# schematic.net
KiCad netlist of a schematic drawn in EasyEDA
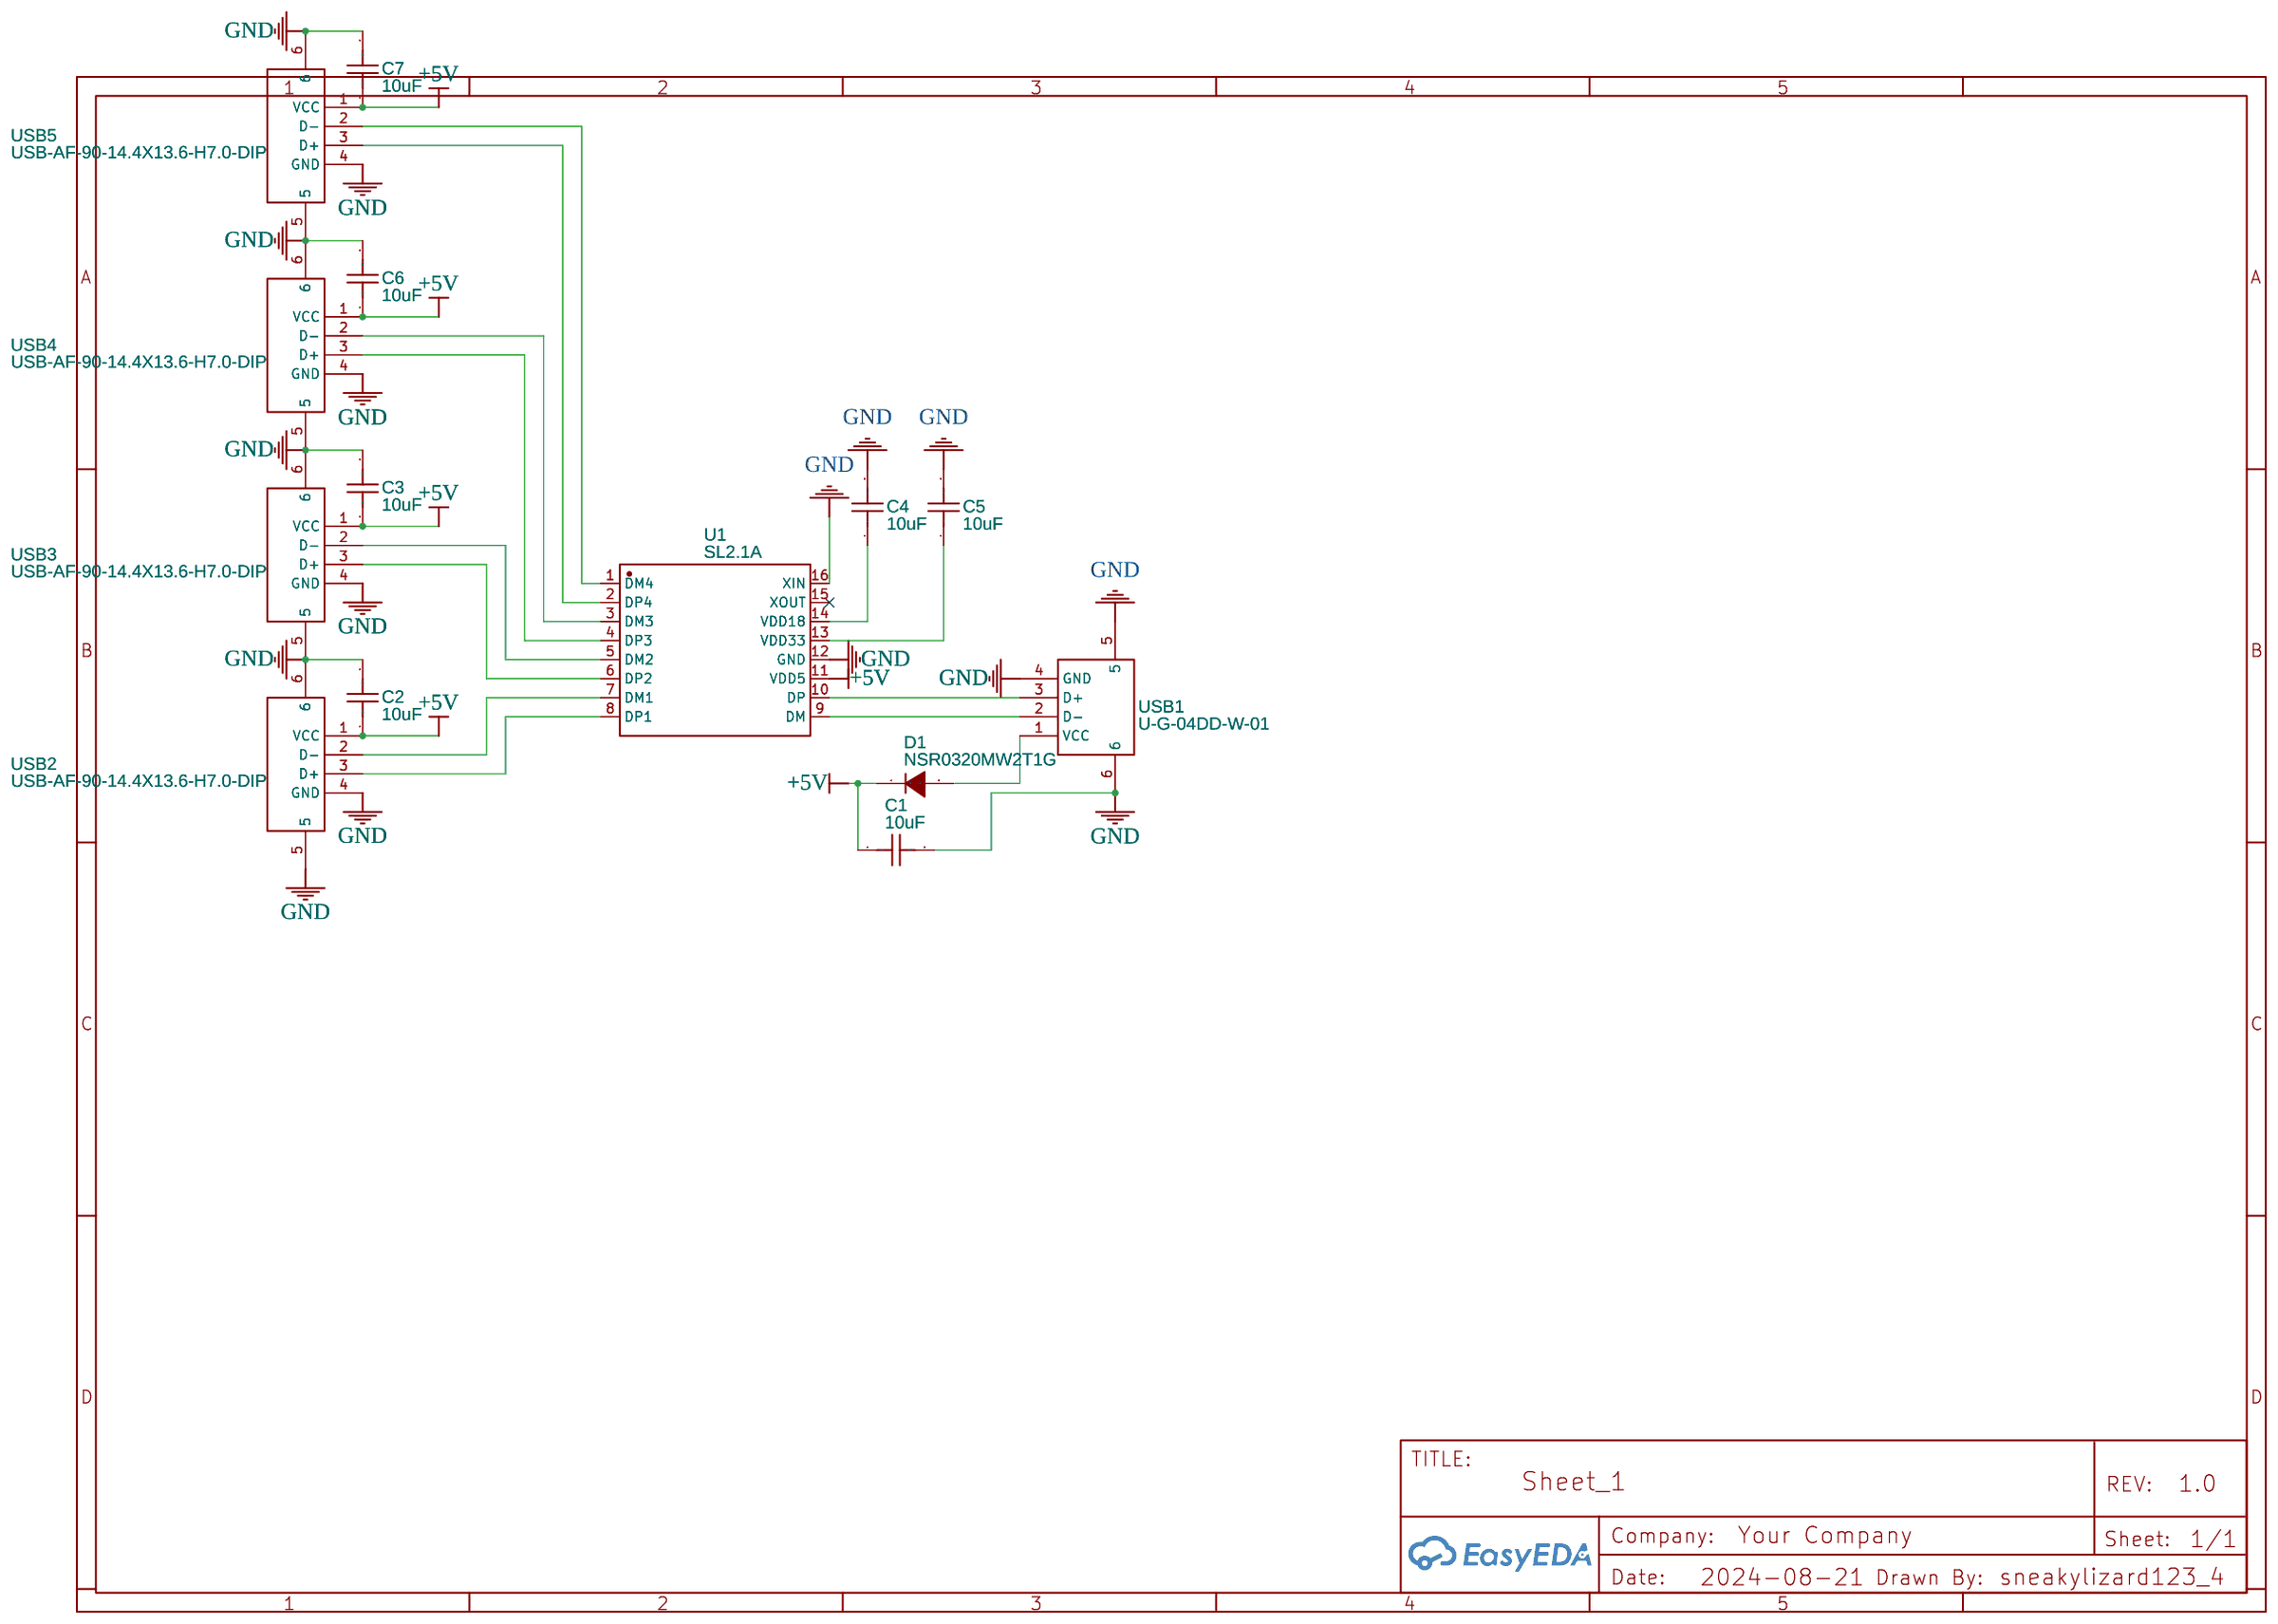
[diagram p0: schematic sheet]

(export (version "E")
  (design (tool "Eeschema 10.0.6"))
  (components
    (comp (ref "C1")
      (value "10uF")
      (fields
        (field (name "Manufacturer Part") "CL10A106KP8NNNC")
        (field (name "Manufacturer") "SAMSUNG(三星)")
      )
      (libsource (lib "") (part "CL10A106KP8NNNC_1"))
    )
    (comp (ref "C2")
      (value "10uF")
      (fields
        (field (name "Manufacturer Part") "CL10A106KP8NNNC")
        (field (name "Manufacturer") "SAMSUNG(三星)")
      )
      (libsource (lib "") (part "CL10A106KP8NNNC"))
    )
    (comp (ref "C3")
      (value "10uF")
      (fields
        (field (name "Manufacturer Part") "CL10A106KP8NNNC")
        (field (name "Manufacturer") "SAMSUNG(三星)")
      )
      (libsource (lib "") (part "CL10A106KP8NNNC"))
    )
    (comp (ref "C4")
      (value "10uF")
      (fields
        (field (name "Manufacturer Part") "CL10A106KP8NNNC")
        (field (name "Manufacturer") "SAMSUNG(三星)")
      )
      (libsource (lib "") (part "CL10A106KP8NNNC"))
    )
    (comp (ref "C5")
      (value "10uF")
      (fields
        (field (name "Manufacturer Part") "CL10A106KP8NNNC")
        (field (name "Manufacturer") "SAMSUNG(三星)")
      )
      (libsource (lib "") (part "CL10A106KP8NNNC"))
    )
    (comp (ref "C6")
      (value "10uF")
      (fields
        (field (name "Manufacturer Part") "CL10A106KP8NNNC")
        (field (name "Manufacturer") "SAMSUNG(三星)")
      )
      (libsource (lib "") (part "CL10A106KP8NNNC"))
    )
    (comp (ref "C7")
      (value "10uF")
      (fields
        (field (name "Manufacturer Part") "CL10A106KP8NNNC")
        (field (name "Manufacturer") "SAMSUNG(三星)")
      )
      (libsource (lib "") (part "CL10A106KP8NNNC"))
    )
    (comp (ref "D1")
      (value "NSR0320MW2T1G")
      (fields (field (name "Manufacturer") "onsemi(安森美)"))
      (libsource (lib "") (part "NSR0320MW2T1G"))
    )
    (comp (ref "U1")
      (value "SL2.1A")
      (fields (field (name "Manufacturer") "CoreChips(和芯润德)"))
      (libsource (lib "") (part "SL2.1A"))
    )
    (comp (ref "USB1")
      (value "U-G-04DD-W-01")
      (fields (field (name "Manufacturer Part") "U-G-O4DD-W-1") (field (name "Manufacturer") "韩国韩荣"))
      (libsource (lib "") (part "U-G-04DD-W-01"))
    )
    (comp (ref "USB2")
      (value "USB-AF-90-14.4X13.6-H7.0-DIP")
      (fields (field (name "Manufacturer Part") "903-131A1011D10100") (field (name "Manufacturer") "精拓金"))
      (libsource (lib "") (part "USB-AF-90-14.4X13.6-H7.0-DIP"))
    )
    (comp (ref "USB3")
      (value "USB-AF-90-14.4X13.6-H7.0-DIP")
      (fields (field (name "Manufacturer Part") "903-131A1011D10100") (field (name "Manufacturer") "精拓金"))
      (libsource (lib "") (part "USB-AF-90-14.4X13.6-H7.0-DIP"))
    )
    (comp (ref "USB4")
      (value "USB-AF-90-14.4X13.6-H7.0-DIP")
      (fields (field (name "Manufacturer Part") "903-131A1011D10100") (field (name "Manufacturer") "精拓金"))
      (libsource (lib "") (part "USB-AF-90-14.4X13.6-H7.0-DIP"))
    )
    (comp (ref "USB5")
      (value "USB-AF-90-14.4X13.6-H7.0-DIP")
      (fields (field (name "Manufacturer Part") "903-131A1011D10100") (field (name "Manufacturer") "精拓金"))
      (libsource (lib "") (part "USB-AF-90-14.4X13.6-H7.0-DIP"))
    )
  )
  (nets
    (net (code "1") (name "+5V") (class "Default")
      (node (ref "C1") (pin "1") (pinfunction "1_1") (pintype "unspecified"))
      (node (ref "C2") (pin "1") (pinfunction "1_1") (pintype "unspecified"))
      (node (ref "C3") (pin "1") (pinfunction "1_1") (pintype "unspecified"))
      (node (ref "C6") (pin "1") (pinfunction "1_1") (pintype "unspecified"))
      (node (ref "C7") (pin "1") (pinfunction "1_1") (pintype "unspecified"))
      (node (ref "D1") (pin "1") (pinfunction "C_1") (pintype "unspecified"))
      (node (ref "U1") (pin "11") (pinfunction "VDD5_11") (pintype "unspecified"))
      (node (ref "USB2") (pin "1") (pinfunction "VCC_1") (pintype "unspecified"))
      (node (ref "USB3") (pin "1") (pinfunction "VCC_1") (pintype "unspecified"))
      (node (ref "USB4") (pin "1") (pinfunction "VCC_1") (pintype "unspecified"))
      (node (ref "USB5") (pin "1") (pinfunction "VCC_1") (pintype "unspecified"))
    )
    (net (code "2") (name "GND") (class "Default")
      (node (ref "C1") (pin "2") (pinfunction "2_2") (pintype "unspecified"))
      (node (ref "C2") (pin "2") (pinfunction "2_2") (pintype "unspecified"))
      (node (ref "C3") (pin "2") (pinfunction "2_2") (pintype "unspecified"))
      (node (ref "C4") (pin "2") (pinfunction "2_2") (pintype "unspecified"))
      (node (ref "C5") (pin "2") (pinfunction "2_2") (pintype "unspecified"))
      (node (ref "C6") (pin "2") (pinfunction "2_2") (pintype "unspecified"))
      (node (ref "C7") (pin "2") (pinfunction "2_2") (pintype "unspecified"))
      (node (ref "U1") (pin "12") (pinfunction "GND_12") (pintype "unspecified"))
      (node (ref "U1") (pin "16") (pinfunction "XIN_16") (pintype "unspecified"))
      (node (ref "USB1") (pin "4") (pinfunction "GND_4") (pintype "unspecified"))
      (node (ref "USB1") (pin "5") (pinfunction "5_5") (pintype "unspecified"))
      (node (ref "USB1") (pin "6") (pinfunction "6_6") (pintype "unspecified"))
      (node (ref "USB2") (pin "4") (pinfunction "GND_4") (pintype "unspecified"))
      (node (ref "USB2") (pin "5") (pinfunction "5_5") (pintype "unspecified"))
      (node (ref "USB2") (pin "6") (pinfunction "6_6") (pintype "unspecified"))
      (node (ref "USB3") (pin "4") (pinfunction "GND_4") (pintype "unspecified"))
      (node (ref "USB3") (pin "5") (pinfunction "5_5") (pintype "unspecified"))
      (node (ref "USB3") (pin "6") (pinfunction "6_6") (pintype "unspecified"))
      (node (ref "USB4") (pin "4") (pinfunction "GND_4") (pintype "unspecified"))
      (node (ref "USB4") (pin "5") (pinfunction "5_5") (pintype "unspecified"))
      (node (ref "USB4") (pin "6") (pinfunction "6_6") (pintype "unspecified"))
      (node (ref "USB5") (pin "4") (pinfunction "GND_4") (pintype "unspecified"))
      (node (ref "USB5") (pin "5") (pinfunction "5_5") (pintype "unspecified"))
      (node (ref "USB5") (pin "6") (pinfunction "6_6") (pintype "unspecified"))
    )
    (net (code "3") (name "Net-(D1-A)") (class "Default")
      (node (ref "D1") (pin "2") (pinfunction "A_2") (pintype "unspecified"))
      (node (ref "USB1") (pin "1") (pinfunction "VCC_1") (pintype "unspecified"))
    )
    (net (code "4") (name "Net-(U1-DM)") (class "Default")
      (node (ref "U1") (pin "9") (pinfunction "DM_9") (pintype "unspecified"))
      (node (ref "USB1") (pin "2") (pinfunction "D-_2") (pintype "unspecified"))
    )
    (net (code "5") (name "Net-(U1-DM1)") (class "Default")
      (node (ref "U1") (pin "7") (pinfunction "DM1_7") (pintype "unspecified"))
      (node (ref "USB2") (pin "2") (pinfunction "D-_2") (pintype "unspecified"))
    )
    (net (code "6") (name "Net-(U1-DM2)") (class "Default")
      (node (ref "U1") (pin "5") (pinfunction "DM2_5") (pintype "unspecified"))
      (node (ref "USB3") (pin "2") (pinfunction "D-_2") (pintype "unspecified"))
    )
    (net (code "7") (name "Net-(U1-DM3)") (class "Default")
      (node (ref "U1") (pin "3") (pinfunction "DM3_3") (pintype "unspecified"))
      (node (ref "USB4") (pin "2") (pinfunction "D-_2") (pintype "unspecified"))
    )
    (net (code "8") (name "Net-(U1-DM4)") (class "Default")
      (node (ref "U1") (pin "1") (pinfunction "DM4_1") (pintype "unspecified"))
      (node (ref "USB5") (pin "2") (pinfunction "D-_2") (pintype "unspecified"))
    )
    (net (code "9") (name "Net-(U1-DP)") (class "Default")
      (node (ref "U1") (pin "10") (pinfunction "DP_10") (pintype "unspecified"))
      (node (ref "USB1") (pin "3") (pinfunction "D+_3") (pintype "unspecified"))
    )
    (net (code "10") (name "Net-(U1-DP1)") (class "Default")
      (node (ref "U1") (pin "8") (pinfunction "DP1_8") (pintype "unspecified"))
      (node (ref "USB2") (pin "3") (pinfunction "D+_3") (pintype "unspecified"))
    )
    (net (code "11") (name "Net-(U1-DP2)") (class "Default")
      (node (ref "U1") (pin "6") (pinfunction "DP2_6") (pintype "unspecified"))
      (node (ref "USB3") (pin "3") (pinfunction "D+_3") (pintype "unspecified"))
    )
    (net (code "12") (name "Net-(U1-DP3)") (class "Default")
      (node (ref "U1") (pin "4") (pinfunction "DP3_4") (pintype "unspecified"))
      (node (ref "USB4") (pin "3") (pinfunction "D+_3") (pintype "unspecified"))
    )
    (net (code "13") (name "Net-(U1-DP4)") (class "Default")
      (node (ref "U1") (pin "2") (pinfunction "DP4_2") (pintype "unspecified"))
      (node (ref "USB5") (pin "3") (pinfunction "D+_3") (pintype "unspecified"))
    )
    (net (code "14") (name "Net-(U1-VDD18)") (class "Default")
      (node (ref "C4") (pin "1") (pinfunction "1_1") (pintype "unspecified"))
      (node (ref "U1") (pin "14") (pinfunction "VDD18_14") (pintype "unspecified"))
    )
    (net (code "15") (name "Net-(U1-VDD33)") (class "Default")
      (node (ref "C5") (pin "1") (pinfunction "1_1") (pintype "unspecified"))
      (node (ref "U1") (pin "13") (pinfunction "VDD33_13") (pintype "unspecified"))
    )
    (net (code "16") (name "unconnected-(U1-XOUT-Pad15)") (class "Default")
      (node (ref "U1") (pin "15") (pinfunction "XOUT_15") (pintype "unspecified+no_connect"))
    )
  )
)
